# L298N_module.net
KiCad netlist of a schematic drawn in EAGLE
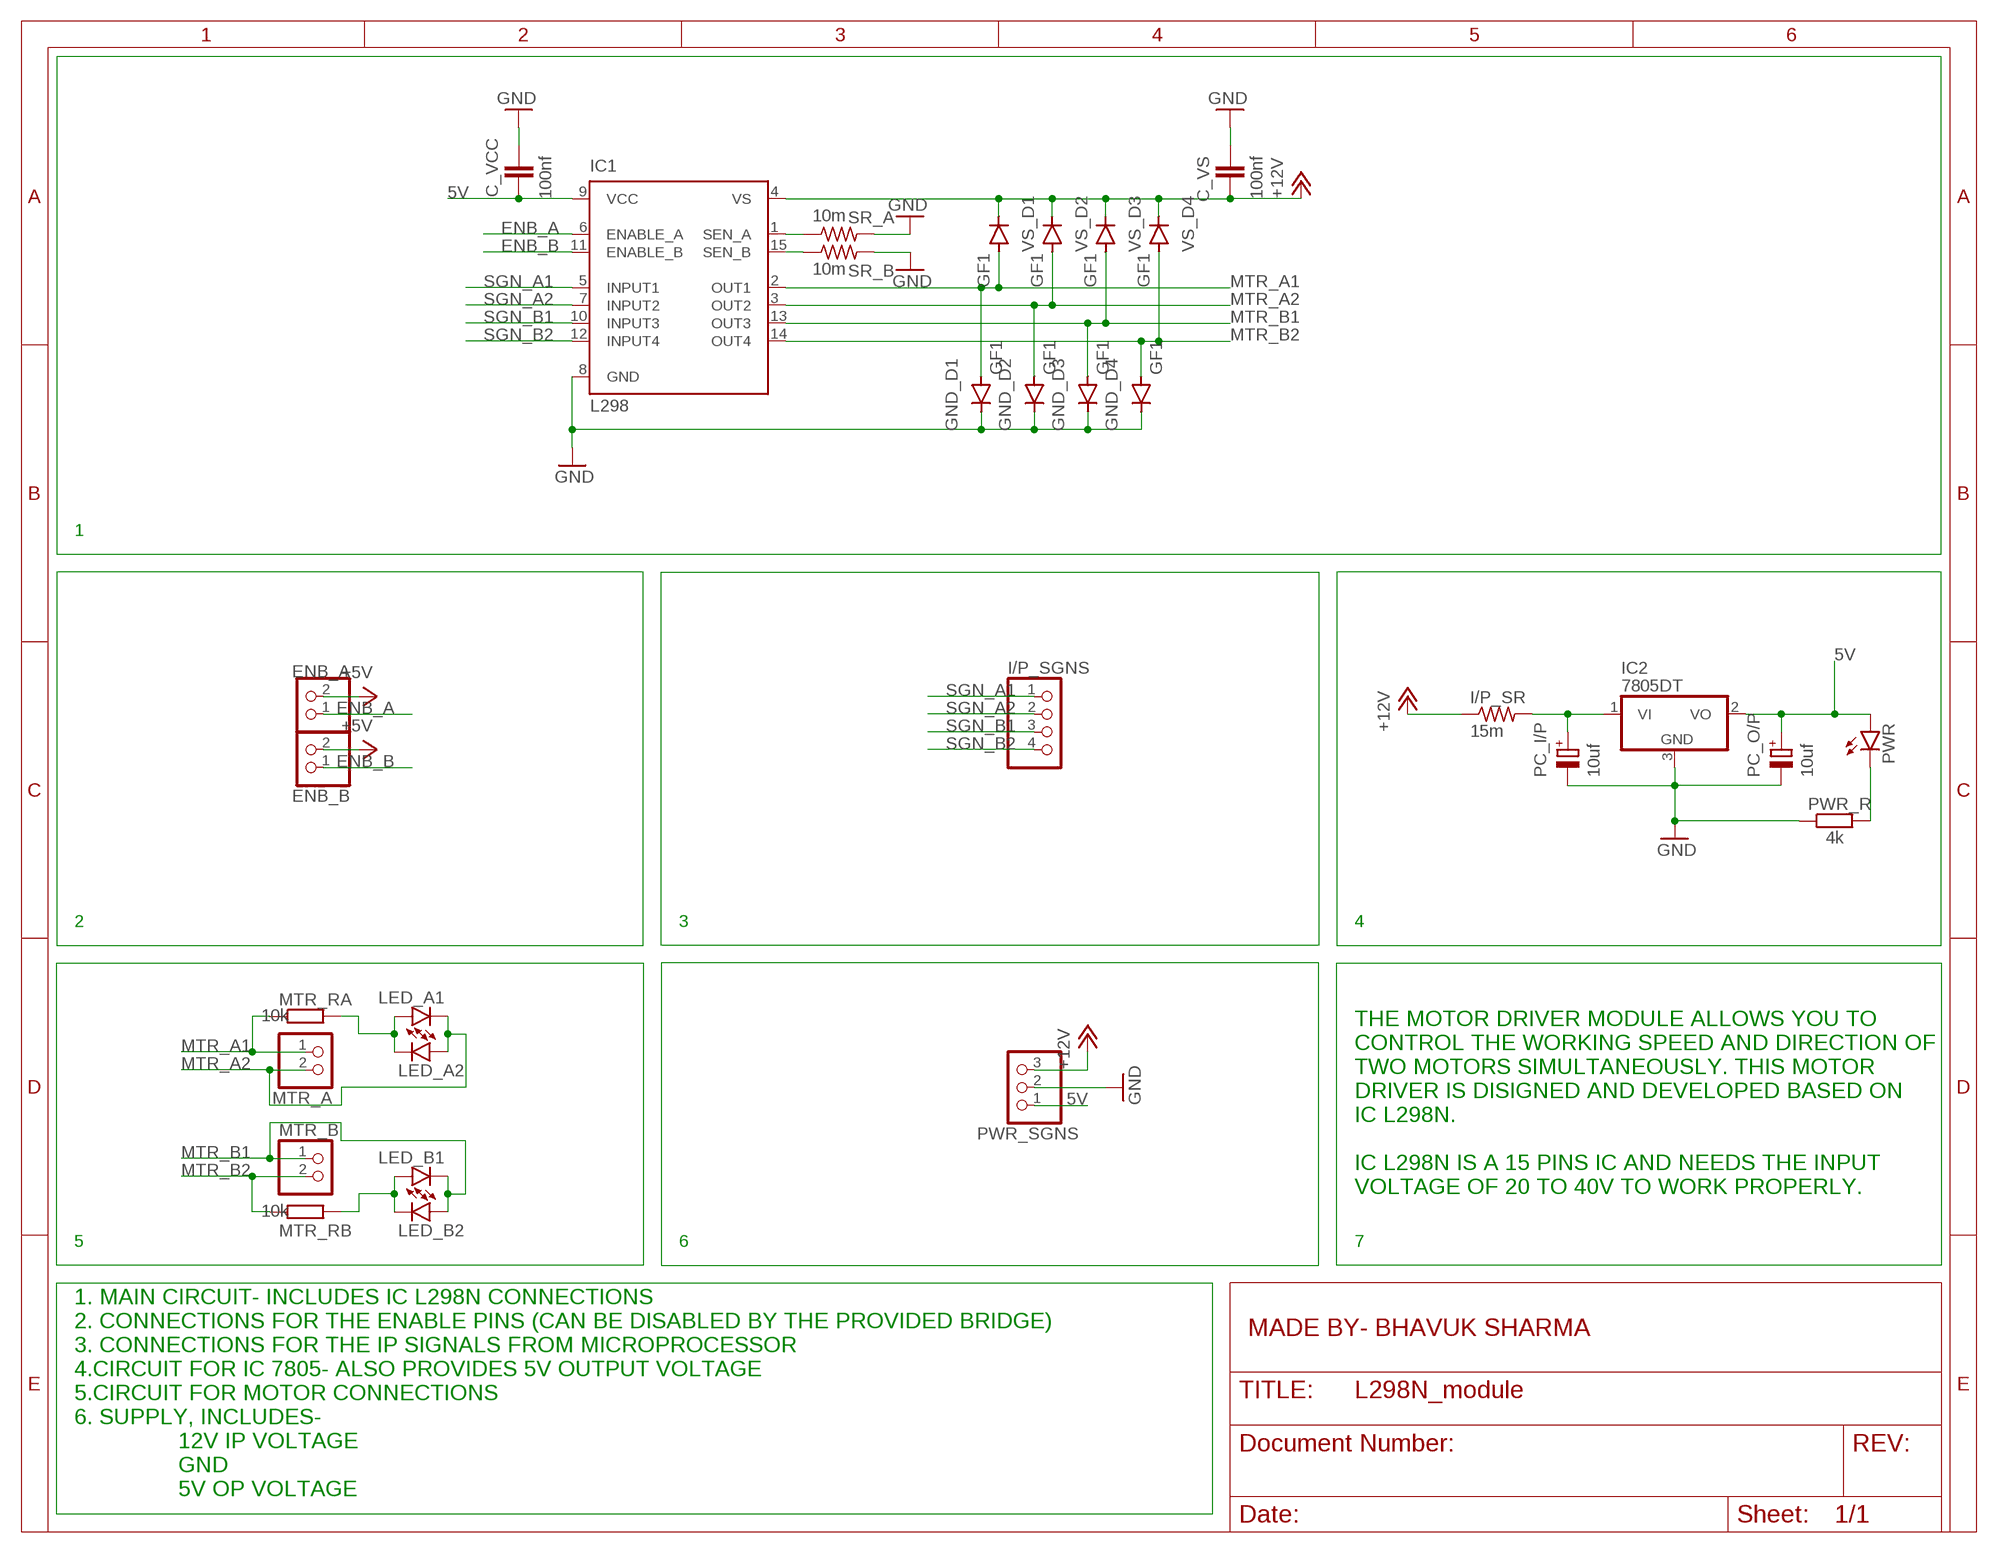
[diagram p0: schematic, sheet 1]

(export (version "E")
  (design (tool "Eeschema 10.0.6"))
  (components
    (comp (ref "C_VCC")
      (value "100nf")
      (footprint "eagle-import:C025-025X050")
      (libsource (lib "eagle-import") (part "C-EU025-025X050"))
    )
    (comp (ref "C_VS")
      (value "100nf")
      (footprint "eagle-import:C025-025X050")
      (libsource (lib "eagle-import") (part "C-EU025-025X050"))
    )
    (comp (ref "ENB_A")
      (value "PINHD-1X2")
      (footprint "eagle-import:1X02")
      (fields (field (name "SPICEPREFIX") "B"))
      (libsource (lib "eagle-import") (part "PINHD-1X2"))
    )
    (comp (ref "ENB_B")
      (value "PINHD-1X2")
      (footprint "eagle-import:1X02")
      (fields (field (name "SPICEPREFIX") "B"))
      (libsource (lib "eagle-import") (part "PINHD-1X2"))
    )
    (comp (ref "GND_D1")
      (value "GF1")
      (footprint "eagle-import:SMA-DO214AC")
      (fields (field (name "SPICEPREFIX") "B"))
      (libsource (lib "eagle-import") (part "GF1"))
    )
    (comp (ref "GND_D2")
      (value "GF1")
      (footprint "eagle-import:SMA-DO214AC")
      (fields (field (name "SPICEPREFIX") "B"))
      (libsource (lib "eagle-import") (part "GF1"))
    )
    (comp (ref "GND_D3")
      (value "GF1")
      (footprint "eagle-import:SMA-DO214AC")
      (fields (field (name "SPICEPREFIX") "B"))
      (libsource (lib "eagle-import") (part "GF1"))
    )
    (comp (ref "GND_D4")
      (value "GF1")
      (footprint "eagle-import:SMA-DO214AC")
      (fields (field (name "SPICEPREFIX") "B"))
      (libsource (lib "eagle-import") (part "GF1"))
    )
    (comp (ref "I/P_SGNS")
      (value "PINHD-1X4")
      (footprint "eagle-import:1X04")
      (fields (field (name "SPICEPREFIX") "E"))
      (libsource (lib "eagle-import") (part "PINHD-1X4"))
    )
    (comp (ref "I/P_SR")
      (value "15m")
      (footprint "eagle-import:0204_7")
      (libsource (lib "eagle-import") (part "R-US_0204/7"))
    )
    (comp (ref "IC1")
      (value "L298")
      (footprint "eagle-import:MULTIWATT-15")
      (fields (field (name "MPN") "L298N") (field (name "SPICEPREFIX") "X"))
      (libsource (lib "eagle-import") (part "L298"))
    )
    (comp (ref "IC2")
      (value "7805DT")
      (footprint "eagle-import:TO252")
      (fields (field (name "SPICEPREFIX") "J"))
      (libsource (lib "eagle-import") (part "78DT05"))
    )
    (comp (ref "LED_A1")
      (value "LEDCHIP-LED0805")
      (footprint "eagle-import:CHIP-LED0805")
      (fields (field (name "SPICEPREFIX") "L"))
      (libsource (lib "eagle-import") (part "LEDCHIP-LED0805"))
    )
    (comp (ref "LED_A2")
      (value "LEDCHIP-LED0805")
      (footprint "eagle-import:CHIP-LED0805")
      (fields (field (name "SPICEPREFIX") "L"))
      (libsource (lib "eagle-import") (part "LEDCHIP-LED0805"))
    )
    (comp (ref "LED_B1")
      (value "LEDCHIP-LED0805")
      (footprint "eagle-import:CHIP-LED0805")
      (fields (field (name "SPICEPREFIX") "L"))
      (libsource (lib "eagle-import") (part "LEDCHIP-LED0805"))
    )
    (comp (ref "LED_B2")
      (value "LEDCHIP-LED0805")
      (footprint "eagle-import:CHIP-LED0805")
      (fields (field (name "SPICEPREFIX") "L"))
      (libsource (lib "eagle-import") (part "LEDCHIP-LED0805"))
    )
    (comp (ref "MTR_A")
      (value "PINHD-1X2")
      (footprint "eagle-import:1X02")
      (fields (field (name "SPICEPREFIX") "B"))
      (libsource (lib "eagle-import") (part "PINHD-1X2"))
    )
    (comp (ref "MTR_B")
      (value "PINHD-1X2")
      (footprint "eagle-import:1X02")
      (fields (field (name "SPICEPREFIX") "B"))
      (libsource (lib "eagle-import") (part "PINHD-1X2"))
    )
    (comp (ref "MTR_RA")
      (value "10k")
      (footprint "eagle-import:0204_7")
      (libsource (lib "eagle-import") (part "R-EU_0204/7"))
    )
    (comp (ref "MTR_RB")
      (value "10k")
      (footprint "eagle-import:0204_7")
      (libsource (lib "eagle-import") (part "R-EU_0204/7"))
    )
    (comp (ref "PC_I/P")
      (value "10uf")
      (footprint "eagle-import:139CLL-2R")
      (libsource (lib "eagle-import") (part "CPOL-EU139CLL-2R"))
    )
    (comp (ref "PC_O/P")
      (value "10uf")
      (footprint "eagle-import:139CLL-2R")
      (libsource (lib "eagle-import") (part "CPOL-EU139CLL-2R"))
    )
    (comp (ref "PWR")
      (value "LED5MM")
      (footprint "eagle-import:LED5MM")
      (fields (field (name "SPICEPREFIX") "B"))
      (libsource (lib "eagle-import") (part "LED5MM"))
    )
    (comp (ref "PWR_R")
      (value "4k")
      (footprint "eagle-import:0204_7")
      (libsource (lib "eagle-import") (part "R-EU_0204/7"))
    )
    (comp (ref "PWR_SGNS")
      (value "PINHD-1X3")
      (footprint "eagle-import:1X03")
      (fields (field (name "SPICEPREFIX") "J"))
      (libsource (lib "eagle-import") (part "PINHD-1X3"))
    )
    (comp (ref "SR_A")
      (value "10m")
      (footprint "eagle-import:0204_7")
      (libsource (lib "eagle-import") (part "R-US_0204/7"))
    )
    (comp (ref "SR_B")
      (value "10m")
      (footprint "eagle-import:0204_7")
      (libsource (lib "eagle-import") (part "R-US_0204/7"))
    )
    (comp (ref "VS_D1")
      (value "GF1")
      (footprint "eagle-import:SMA-DO214AC")
      (fields (field (name "SPICEPREFIX") "B"))
      (libsource (lib "eagle-import") (part "GF1"))
    )
    (comp (ref "VS_D2")
      (value "GF1")
      (footprint "eagle-import:SMA-DO214AC")
      (fields (field (name "SPICEPREFIX") "B"))
      (libsource (lib "eagle-import") (part "GF1"))
    )
    (comp (ref "VS_D3")
      (value "GF1")
      (footprint "eagle-import:SMA-DO214AC")
      (fields (field (name "SPICEPREFIX") "B"))
      (libsource (lib "eagle-import") (part "GF1"))
    )
    (comp (ref "VS_D4")
      (value "GF1")
      (footprint "eagle-import:SMA-DO214AC")
      (fields (field (name "SPICEPREFIX") "B"))
      (libsource (lib "eagle-import") (part "GF1"))
    )
  )
  (nets
    (net (code "1") (name "+5V") (class "Default")
      (node (ref "ENB_A") (pin "2") (pinfunction "2_2") (pintype "passive"))
      (node (ref "ENB_B") (pin "2") (pinfunction "2_2") (pintype "passive"))
    )
    (net (code "2") (name "+12V") (class "Default")
      (node (ref "C_VS") (pin "1") (pinfunction "1_1") (pintype "passive"))
      (node (ref "I/P_SR") (pin "1") (pinfunction "1_1") (pintype "passive"))
      (node (ref "IC1") (pin "4") (pinfunction "VS_4") (pintype "power_in"))
      (node (ref "PWR_SGNS") (pin "3") (pinfunction "3_3") (pintype "passive"))
      (node (ref "VS_D1") (pin "K") (pinfunction "C_K") (pintype "passive"))
      (node (ref "VS_D2") (pin "K") (pinfunction "C_K") (pintype "passive"))
      (node (ref "VS_D3") (pin "K") (pinfunction "C_K") (pintype "passive"))
      (node (ref "VS_D4") (pin "K") (pinfunction "C_K") (pintype "passive"))
    )
    (net (code "3") (name "/5V") (class "Default")
      (node (ref "C_VCC") (pin "1") (pinfunction "1_1") (pintype "passive"))
      (node (ref "IC1") (pin "9") (pinfunction "VCC_9") (pintype "power_in"))
      (node (ref "IC2") (pin "2") (pinfunction "VO_2") (pintype "passive"))
      (node (ref "PC_O/P") (pin "+") (pinfunction "+_+") (pintype "passive"))
      (node (ref "PWR") (pin "A") (pinfunction "A_A") (pintype "passive"))
      (node (ref "PWR_SGNS") (pin "1") (pinfunction "1_1") (pintype "passive"))
    )
    (net (code "4") (name "/ENB_A") (class "Default")
      (node (ref "ENB_A") (pin "1") (pinfunction "1_1") (pintype "passive"))
      (node (ref "IC1") (pin "6") (pinfunction "ENABLE_A_6") (pintype "input"))
    )
    (net (code "5") (name "/ENB_B") (class "Default")
      (node (ref "ENB_B") (pin "1") (pinfunction "1_1") (pintype "passive"))
      (node (ref "IC1") (pin "11") (pinfunction "ENABLE_B_11") (pintype "input"))
    )
    (net (code "6") (name "/MTR_A1") (class "Default")
      (node (ref "GND_D1") (pin "A") (pinfunction "A_A") (pintype "passive"))
      (node (ref "IC1") (pin "2") (pinfunction "OUT1_2") (pintype "output"))
      (node (ref "MTR_A") (pin "1") (pinfunction "1_1") (pintype "passive"))
      (node (ref "MTR_RA") (pin "1") (pinfunction "1_1") (pintype "passive"))
      (node (ref "VS_D1") (pin "A") (pinfunction "A_A") (pintype "passive"))
    )
    (net (code "7") (name "/MTR_A2") (class "Default")
      (node (ref "GND_D2") (pin "A") (pinfunction "A_A") (pintype "passive"))
      (node (ref "IC1") (pin "3") (pinfunction "OUT2_3") (pintype "output"))
      (node (ref "LED_A1") (pin "C") (pinfunction "C_C") (pintype "passive"))
      (node (ref "LED_A2") (pin "A") (pinfunction "A_A") (pintype "passive"))
      (node (ref "MTR_A") (pin "2") (pinfunction "2_2") (pintype "passive"))
      (node (ref "VS_D2") (pin "A") (pinfunction "A_A") (pintype "passive"))
    )
    (net (code "8") (name "/MTR_B1") (class "Default")
      (node (ref "GND_D3") (pin "A") (pinfunction "A_A") (pintype "passive"))
      (node (ref "IC1") (pin "13") (pinfunction "OUT3_13") (pintype "output"))
      (node (ref "LED_B1") (pin "C") (pinfunction "C_C") (pintype "passive"))
      (node (ref "LED_B2") (pin "A") (pinfunction "A_A") (pintype "passive"))
      (node (ref "MTR_B") (pin "1") (pinfunction "1_1") (pintype "passive"))
      (node (ref "VS_D3") (pin "A") (pinfunction "A_A") (pintype "passive"))
    )
    (net (code "9") (name "/MTR_B2") (class "Default")
      (node (ref "GND_D4") (pin "A") (pinfunction "A_A") (pintype "passive"))
      (node (ref "IC1") (pin "14") (pinfunction "OUT4_14") (pintype "output"))
      (node (ref "MTR_B") (pin "2") (pinfunction "2_2") (pintype "passive"))
      (node (ref "MTR_RB") (pin "1") (pinfunction "1_1") (pintype "passive"))
      (node (ref "VS_D4") (pin "A") (pinfunction "A_A") (pintype "passive"))
    )
    (net (code "10") (name "/SGN_A1") (class "Default")
      (node (ref "I/P_SGNS") (pin "1") (pinfunction "1_1") (pintype "passive"))
      (node (ref "IC1") (pin "5") (pinfunction "INPUT1_5") (pintype "input"))
    )
    (net (code "11") (name "/SGN_A2") (class "Default")
      (node (ref "I/P_SGNS") (pin "2") (pinfunction "2_2") (pintype "passive"))
      (node (ref "IC1") (pin "7") (pinfunction "INPUT2_7") (pintype "input"))
    )
    (net (code "12") (name "/SGN_B1") (class "Default")
      (node (ref "I/P_SGNS") (pin "3") (pinfunction "3_3") (pintype "passive"))
      (node (ref "IC1") (pin "10") (pinfunction "INPUT3_10") (pintype "input"))
    )
    (net (code "13") (name "/SGN_B2") (class "Default")
      (node (ref "I/P_SGNS") (pin "4") (pinfunction "4_4") (pintype "passive"))
      (node (ref "IC1") (pin "12") (pinfunction "INPUT4_12") (pintype "input"))
    )
    (net (code "14") (name "GND") (class "Default")
      (node (ref "C_VCC") (pin "2") (pinfunction "2_2") (pintype "passive"))
      (node (ref "C_VS") (pin "2") (pinfunction "2_2") (pintype "passive"))
      (node (ref "GND_D1") (pin "K") (pinfunction "C_K") (pintype "passive"))
      (node (ref "GND_D2") (pin "K") (pinfunction "C_K") (pintype "passive"))
      (node (ref "GND_D3") (pin "K") (pinfunction "C_K") (pintype "passive"))
      (node (ref "GND_D4") (pin "K") (pinfunction "C_K") (pintype "passive"))
      (node (ref "IC1") (pin "8") (pinfunction "GND_8") (pintype "power_in"))
      (node (ref "IC2") (pin "3") (pinfunction "GND_3") (pintype "passive"))
      (node (ref "PC_I/P") (pin "-") (pinfunction "-_-") (pintype "passive"))
      (node (ref "PC_O/P") (pin "-") (pinfunction "-_-") (pintype "passive"))
      (node (ref "PWR_R") (pin "1") (pinfunction "1_1") (pintype "passive"))
      (node (ref "PWR_SGNS") (pin "2") (pinfunction "2_2") (pintype "passive"))
      (node (ref "SR_A") (pin "2") (pinfunction "2_2") (pintype "passive"))
      (node (ref "SR_B") (pin "2") (pinfunction "2_2") (pintype "passive"))
    )
    (net (code "15") (name "Net-(IC1-SEN_A)") (class "Default")
      (node (ref "IC1") (pin "1") (pinfunction "SEN_A_1") (pintype "input"))
      (node (ref "SR_A") (pin "1") (pinfunction "1_1") (pintype "passive"))
    )
    (net (code "16") (name "Net-(IC1-SEN_B)") (class "Default")
      (node (ref "IC1") (pin "15") (pinfunction "SEN_B_15") (pintype "input"))
      (node (ref "SR_B") (pin "1") (pinfunction "1_1") (pintype "passive"))
    )
    (net (code "17") (name "Net-(IC2-VI)") (class "Default")
      (node (ref "I/P_SR") (pin "2") (pinfunction "2_2") (pintype "passive"))
      (node (ref "IC2") (pin "1") (pinfunction "VI_1") (pintype "input"))
      (node (ref "PC_I/P") (pin "+") (pinfunction "+_+") (pintype "passive"))
    )
    (net (code "18") (name "Net-(LED_A1-PadA)") (class "Default")
      (node (ref "LED_A1") (pin "A") (pinfunction "A_A") (pintype "passive"))
      (node (ref "LED_A2") (pin "C") (pinfunction "C_C") (pintype "passive"))
      (node (ref "MTR_RA") (pin "2") (pinfunction "2_2") (pintype "passive"))
    )
    (net (code "19") (name "Net-(LED_B1-PadA)") (class "Default")
      (node (ref "LED_B1") (pin "A") (pinfunction "A_A") (pintype "passive"))
      (node (ref "LED_B2") (pin "C") (pinfunction "C_C") (pintype "passive"))
      (node (ref "MTR_RB") (pin "2") (pinfunction "2_2") (pintype "passive"))
    )
    (net (code "20") (name "Net-(PWR-C)") (class "Default")
      (node (ref "PWR") (pin "K") (pinfunction "C_K") (pintype "passive"))
      (node (ref "PWR_R") (pin "2") (pinfunction "2_2") (pintype "passive"))
    )
  )
)
